# ESP32_DevKitC_v4.net
KiCad netlist of a schematic drawn in Altium Designer
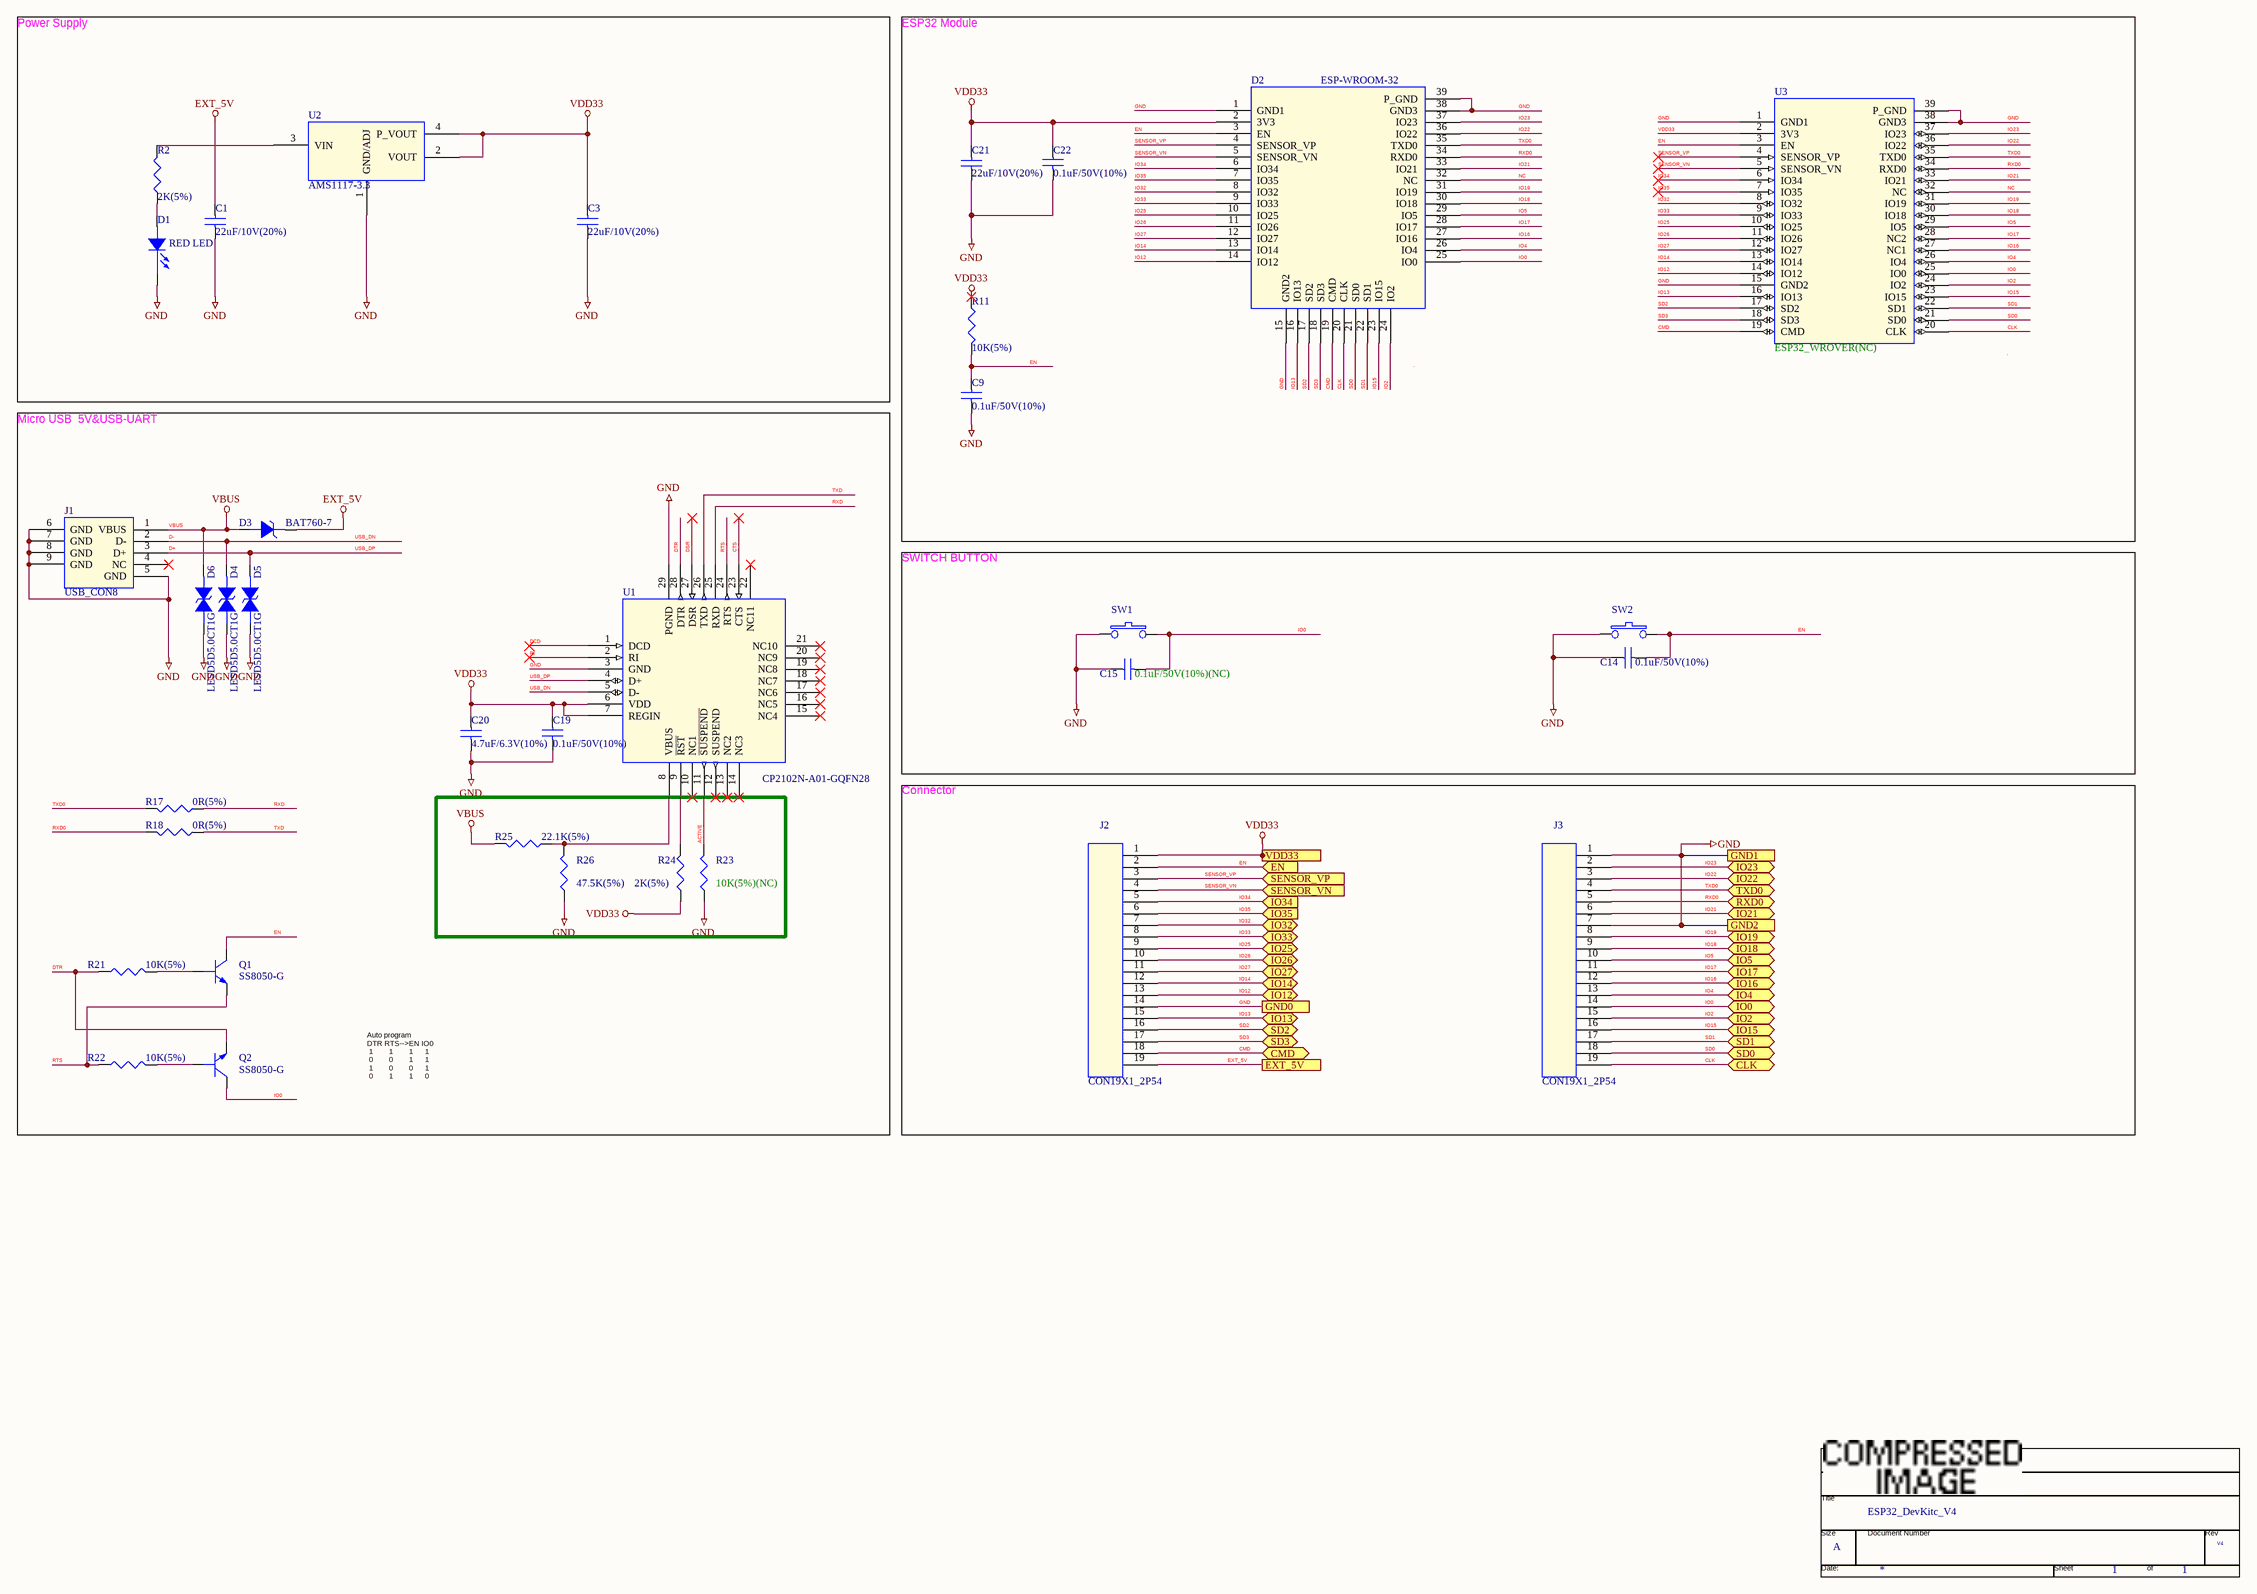
[diagram p0: ESP32_DevKitC_v4.SchDoc]

(export (version "E")
  (design (tool "Eeschema 10.0.6"))
  (components
    (comp (ref "*")
      (value "TitleBlock0")
      (fields
        (field (name "REVCODE") "V4")
        (field (name "TITLE") "ESP32_DevKitc_V4")
        (field (name "PAGE SIZE") "A")
        (field (name "PAGE NUMBER") "1")
        (field (name "PAGE COUNT") "1")
      )
      (libsource (lib "*") (part "TitleBlock0"))
    )
    (comp (ref "C1") (value "22uF/10V(20%)") (footprint "C0603") (libsource (lib "*") (part "CAP NP")))
    (comp (ref "C3") (value "22uF/10V(20%)") (footprint "C0603") (libsource (lib "*") (part "CAP NP")))
    (comp (ref "C9") (value "0.1uF/50V(10%)") (footprint "C0402") (libsource (lib "*") (part "CAP NP")))
    (comp (ref "C14") (value "0.1uF/50V(10%)") (footprint "C0402") (libsource (lib "*") (part "CAP NP")))
    (comp (ref "C15") (value "0.1uF/50V(10%)(NC)") (footprint "C0402") (libsource (lib "*") (part "CAP NP")))
    (comp (ref "C19") (value "0.1uF/50V(10%)") (footprint "C0402") (libsource (lib "*") (part "CAP NP")))
    (comp (ref "C20") (value "4.7uF/6.3V(10%)") (footprint "C0402") (libsource (lib "*") (part "CAP NP")))
    (comp (ref "C21") (value "22uF/10V(20%)") (footprint "C0603") (libsource (lib "*") (part "CAP NP")))
    (comp (ref "C22") (value "0.1uF/50V(10%)") (footprint "C0402") (libsource (lib "*") (part "CAP NP")))
    (comp (ref "D1") (value "RED LED") (footprint "0603D/A") (libsource (lib "*") (part "LED_1")))
    (comp (ref "D2")
      (value "ESP-WROOM-32")
      (footprint "ESP32_MODULE")
      (libsource (lib "*") (part "ESP32_MODULE_2"))
    )
    (comp (ref "D3") (value "BAT760-7") (footprint "SOD323") (libsource (lib "*") (part "DIODE_POWER_0")))
    (comp (ref "D4")
      (value "LESD5D5.0CT1G")
      (footprint "ESD0402")
      (libsource (lib "*") (part "DIODE BI-DIR TRIG"))
    )
    (comp (ref "D5")
      (value "LESD5D5.0CT1G")
      (footprint "ESD0402")
      (libsource (lib "*") (part "DIODE BI-DIR TRIG"))
    )
    (comp (ref "D6")
      (value "LESD5D5.0CT1G")
      (footprint "ESD0402")
      (libsource (lib "*") (part "DIODE BI-DIR TRIG"))
    )
    (comp (ref "J1") (value "USB_CON8") (footprint "USB_5P") (libsource (lib "*") (part "CON4_2")))
    (comp (ref "J2") (value "CON19X1_2P54") (footprint "CON19_2P54") (libsource (lib "*") (part "CON19_0")))
    (comp (ref "J3") (value "CON19X1_2P54") (footprint "CON19_2P54") (libsource (lib "*") (part "CON19_0")))
    (comp (ref "Q1") (value "SS8050-G") (footprint "SOT-23-3") (libsource (lib "*") (part "NPN BCE_0")))
    (comp (ref "Q2") (value "SS8050-G") (footprint "SOT-23-3") (libsource (lib "*") (part "NPN BCE_0")))
    (comp (ref "R2") (value "2K(5%)") (footprint "R0402") (libsource (lib "*") (part "RESISTOR_0")))
    (comp (ref "R11") (value "10K(5%)") (footprint "R0402") (libsource (lib "*") (part "RESISTOR_0")))
    (comp (ref "R17") (value "0R(5%)") (footprint "R0402") (libsource (lib "*") (part "RESISTOR_0")))
    (comp (ref "R18") (value "0R(5%)") (footprint "R0402") (libsource (lib "*") (part "RESISTOR_0")))
    (comp (ref "R21") (value "10K(5%)") (footprint "R0402") (libsource (lib "*") (part "RESISTOR_0")))
    (comp (ref "R22") (value "10K(5%)") (footprint "R0402") (libsource (lib "*") (part "RESISTOR_0")))
    (comp (ref "R23") (value "10K(5%)(NC)") (footprint "R0402") (libsource (lib "*") (part "RESISTOR_0")))
    (comp (ref "R24") (value "2K(5%)") (footprint "R0402") (libsource (lib "*") (part "RESISTOR_0")))
    (comp (ref "R25") (value "22.1K(5%)") (footprint "R0402") (libsource (lib "*") (part "RESISTOR_0")))
    (comp (ref "R26") (value "47.5K(5%)") (footprint "R0402") (libsource (lib "*") (part "RESISTOR_0")))
    (comp (ref "SW1")
      (value "SW PUSHBUTTON")
      (footprint "SW_3X4X2MM")
      (libsource (lib "*") (part "SW PUSHBUTTON"))
    )
    (comp (ref "SW2")
      (value "SW PUSHBUTTON")
      (footprint "SW_3X4X2MM")
      (libsource (lib "*") (part "SW PUSHBUTTON"))
    )
    (comp (ref "U1")
      (value "CP2102N-A01-GQFN28")
      (footprint "CP2102_QFN_28P")
      (libsource (lib "*") (part "CP2102_QFN_28"))
    )
    (comp (ref "U2") (value "AMS1117-3.3") (footprint "SOT-223") (libsource (lib "*") (part "NCP1117_0")))
    (comp (ref "U3")
      (value "ESP32_WROVER(NC)")
      (footprint "ESP32_MODULE_2COL")
      (libsource (lib "*") (part "ESP32_MODULE_3"))
    )
  )
  (nets
    (net (code "1") (name "/ACTIVE") (class "Default")
      (node (ref "R23") (pin "2") (pinfunction "2_2") (pintype "passive"))
      (node (ref "U1") (pin "11") (pinfunction "~{SUSPEND}_11") (pintype "output"))
    )
    (net (code "2") (name "/CLK") (class "Default")
      (node (ref "D2") (pin "20") (pinfunction "CLK_20") (pintype "passive"))
      (node (ref "J3") (pin "19") (pinfunction "19_19") (pintype "passive"))
      (node (ref "U3") (pin "20") (pinfunction "CLK_20") (pintype "bidirectional"))
    )
    (net (code "3") (name "/CMD") (class "Default")
      (node (ref "D2") (pin "19") (pinfunction "CMD_19") (pintype "passive"))
      (node (ref "J2") (pin "18") (pinfunction "18_18") (pintype "passive"))
      (node (ref "U3") (pin "19") (pinfunction "CMD_19") (pintype "bidirectional"))
    )
    (net (code "4") (name "/CTS") (class "Default")
      (node (ref "U1") (pin "23") (pinfunction "CTS_23") (pintype "input+no_connect"))
    )
    (net (code "5") (name "/D+") (class "Default")
      (node (ref "D5") (pin "1") (pinfunction "1_1") (pintype "passive"))
      (node (ref "J1") (pin "3") (pinfunction "D+_3") (pintype "passive"))
      (node (ref "U1") (pin "4") (pinfunction "D+_4") (pintype "bidirectional"))
    )
    (net (code "6") (name "/D-") (class "Default")
      (node (ref "D4") (pin "1") (pinfunction "1_1") (pintype "passive"))
      (node (ref "J1") (pin "2") (pinfunction "D-_2") (pintype "passive"))
      (node (ref "U1") (pin "5") (pinfunction "D-_5") (pintype "bidirectional"))
    )
    (net (code "7") (name "/DCD") (class "Default")
      (node (ref "U1") (pin "1") (pinfunction "DCD_1") (pintype "input+no_connect"))
    )
    (net (code "8") (name "/DSR") (class "Default")
      (node (ref "U1") (pin "27") (pinfunction "DSR_27") (pintype "input+no_connect"))
    )
    (net (code "9") (name "/DTR") (class "Default")
      (node (ref "Q2") (pin "2") (pinfunction "E_2") (pintype "passive"))
      (node (ref "R21") (pin "1") (pinfunction "1_1") (pintype "passive"))
      (node (ref "U1") (pin "28") (pinfunction "DTR_28") (pintype "output"))
    )
    (net (code "10") (name "/EN") (class "Default")
      (node (ref "C14") (pin "2") (pinfunction "2_2") (pintype "passive"))
      (node (ref "C9") (pin "1") (pinfunction "1_1") (pintype "passive"))
      (node (ref "D2") (pin "3") (pinfunction "EN_3") (pintype "passive"))
      (node (ref "J2") (pin "2") (pinfunction "2_2") (pintype "passive"))
      (node (ref "Q1") (pin "3") (pinfunction "C_3") (pintype "passive"))
      (node (ref "R11") (pin "2") (pinfunction "2_2") (pintype "passive"))
      (node (ref "SW2") (pin "2") (pinfunction "2_2") (pintype "passive"))
      (node (ref "U3") (pin "3") (pinfunction "EN_3") (pintype "passive"))
    )
    (net (code "11") (name "/IO0") (class "Default")
      (node (ref "C15") (pin "2") (pinfunction "2_2") (pintype "passive"))
      (node (ref "D2") (pin "25") (pinfunction "IO0_25") (pintype "passive"))
      (node (ref "J3") (pin "14") (pinfunction "14_14") (pintype "passive"))
      (node (ref "Q2") (pin "3") (pinfunction "C_3") (pintype "passive"))
      (node (ref "SW1") (pin "2") (pinfunction "2_2") (pintype "passive"))
      (node (ref "U3") (pin "25") (pinfunction "IO0_25") (pintype "bidirectional"))
    )
    (net (code "12") (name "/IO2") (class "Default")
      (node (ref "D2") (pin "24") (pinfunction "IO2_24") (pintype "passive"))
      (node (ref "J3") (pin "15") (pinfunction "15_15") (pintype "passive"))
      (node (ref "U3") (pin "24") (pinfunction "IO2_24") (pintype "bidirectional"))
    )
    (net (code "13") (name "/IO4") (class "Default")
      (node (ref "D2") (pin "26") (pinfunction "IO4_26") (pintype "passive"))
      (node (ref "J3") (pin "13") (pinfunction "13_13") (pintype "passive"))
      (node (ref "U3") (pin "26") (pinfunction "IO4_26") (pintype "bidirectional"))
    )
    (net (code "14") (name "/IO5") (class "Default")
      (node (ref "D2") (pin "29") (pinfunction "IO5_29") (pintype "passive"))
      (node (ref "J3") (pin "10") (pinfunction "10_10") (pintype "passive"))
      (node (ref "U3") (pin "29") (pinfunction "IO5_29") (pintype "bidirectional"))
    )
    (net (code "15") (name "/IO12") (class "Default")
      (node (ref "D2") (pin "14") (pinfunction "IO12_14") (pintype "passive"))
      (node (ref "J2") (pin "13") (pinfunction "13_13") (pintype "passive"))
      (node (ref "U3") (pin "14") (pinfunction "IO12_14") (pintype "bidirectional"))
    )
    (net (code "16") (name "/IO13") (class "Default")
      (node (ref "D2") (pin "16") (pinfunction "IO13_16") (pintype "passive"))
      (node (ref "J2") (pin "15") (pinfunction "15_15") (pintype "passive"))
      (node (ref "U3") (pin "16") (pinfunction "IO13_16") (pintype "bidirectional"))
    )
    (net (code "17") (name "/IO14") (class "Default")
      (node (ref "D2") (pin "13") (pinfunction "IO14_13") (pintype "passive"))
      (node (ref "J2") (pin "12") (pinfunction "12_12") (pintype "passive"))
      (node (ref "U3") (pin "13") (pinfunction "IO14_13") (pintype "bidirectional"))
    )
    (net (code "18") (name "/IO15") (class "Default")
      (node (ref "D2") (pin "23") (pinfunction "IO15_23") (pintype "passive"))
      (node (ref "J3") (pin "16") (pinfunction "16_16") (pintype "passive"))
      (node (ref "U3") (pin "23") (pinfunction "IO15_23") (pintype "bidirectional"))
    )
    (net (code "19") (name "/IO16") (class "Default")
      (node (ref "D2") (pin "27") (pinfunction "IO16_27") (pintype "passive"))
      (node (ref "J3") (pin "12") (pinfunction "12_12") (pintype "passive"))
      (node (ref "U3") (pin "27") (pinfunction "NC1_27") (pintype "bidirectional"))
    )
    (net (code "20") (name "/IO17") (class "Default")
      (node (ref "D2") (pin "28") (pinfunction "IO17_28") (pintype "passive"))
      (node (ref "J3") (pin "11") (pinfunction "11_11") (pintype "passive"))
      (node (ref "U3") (pin "28") (pinfunction "NC2_28") (pintype "bidirectional"))
    )
    (net (code "21") (name "/IO18") (class "Default")
      (node (ref "D2") (pin "30") (pinfunction "IO18_30") (pintype "passive"))
      (node (ref "J3") (pin "9") (pinfunction "9_9") (pintype "passive"))
      (node (ref "U3") (pin "30") (pinfunction "IO18_30") (pintype "bidirectional"))
    )
    (net (code "22") (name "/IO19") (class "Default")
      (node (ref "D2") (pin "31") (pinfunction "IO19_31") (pintype "passive"))
      (node (ref "J3") (pin "8") (pinfunction "8_8") (pintype "passive"))
      (node (ref "U3") (pin "31") (pinfunction "IO19_31") (pintype "bidirectional"))
    )
    (net (code "23") (name "/IO21") (class "Default")
      (node (ref "D2") (pin "33") (pinfunction "IO21_33") (pintype "passive"))
      (node (ref "J3") (pin "6") (pinfunction "6_6") (pintype "passive"))
      (node (ref "U3") (pin "33") (pinfunction "IO21_33") (pintype "bidirectional"))
    )
    (net (code "24") (name "/IO22") (class "Default")
      (node (ref "D2") (pin "36") (pinfunction "IO22_36") (pintype "passive"))
      (node (ref "J3") (pin "3") (pinfunction "3_3") (pintype "passive"))
      (node (ref "U3") (pin "36") (pinfunction "IO22_36") (pintype "bidirectional"))
    )
    (net (code "25") (name "/IO23") (class "Default")
      (node (ref "D2") (pin "37") (pinfunction "IO23_37") (pintype "passive"))
      (node (ref "J3") (pin "2") (pinfunction "2_2") (pintype "passive"))
      (node (ref "U3") (pin "37") (pinfunction "IO23_37") (pintype "bidirectional"))
    )
    (net (code "26") (name "/IO25") (class "Default")
      (node (ref "D2") (pin "10") (pinfunction "IO25_10") (pintype "passive"))
      (node (ref "J2") (pin "9") (pinfunction "9_9") (pintype "passive"))
      (node (ref "U3") (pin "10") (pinfunction "IO25_10") (pintype "bidirectional"))
    )
    (net (code "27") (name "/IO26") (class "Default")
      (node (ref "D2") (pin "11") (pinfunction "IO26_11") (pintype "passive"))
      (node (ref "J2") (pin "10") (pinfunction "10_10") (pintype "passive"))
      (node (ref "U3") (pin "11") (pinfunction "IO26_11") (pintype "bidirectional"))
    )
    (net (code "28") (name "/IO27") (class "Default")
      (node (ref "D2") (pin "12") (pinfunction "IO27_12") (pintype "passive"))
      (node (ref "J2") (pin "11") (pinfunction "11_11") (pintype "passive"))
      (node (ref "U3") (pin "12") (pinfunction "IO27_12") (pintype "bidirectional"))
    )
    (net (code "29") (name "/IO32") (class "Default")
      (node (ref "D2") (pin "8") (pinfunction "IO32_8") (pintype "passive"))
      (node (ref "J2") (pin "7") (pinfunction "7_7") (pintype "passive"))
      (node (ref "U3") (pin "8") (pinfunction "IO32_8") (pintype "bidirectional"))
    )
    (net (code "30") (name "/IO33") (class "Default")
      (node (ref "D2") (pin "9") (pinfunction "IO33_9") (pintype "passive"))
      (node (ref "J2") (pin "8") (pinfunction "8_8") (pintype "passive"))
      (node (ref "U3") (pin "9") (pinfunction "IO33_9") (pintype "bidirectional"))
    )
    (net (code "31") (name "/IO34") (class "Default")
      (node (ref "D2") (pin "6") (pinfunction "IO34_6") (pintype "passive"))
      (node (ref "J2") (pin "5") (pinfunction "5_5") (pintype "passive"))
      (node (ref "U3") (pin "6") (pinfunction "IO34_6") (pintype "input"))
    )
    (net (code "32") (name "/IO35") (class "Default")
      (node (ref "D2") (pin "7") (pinfunction "IO35_7") (pintype "passive"))
      (node (ref "J2") (pin "6") (pinfunction "6_6") (pintype "passive"))
      (node (ref "U3") (pin "7") (pinfunction "IO35_7") (pintype "input"))
    )
    (net (code "33") (name "/NC") (class "Default")
      (node (ref "D2") (pin "32") (pinfunction "NC_32") (pintype "passive"))
      (node (ref "U3") (pin "32") (pinfunction "NC_32") (pintype "bidirectional"))
    )
    (net (code "34") (name "/RI") (class "Default")
      (node (ref "U1") (pin "2") (pinfunction "RI_2") (pintype "input+no_connect"))
    )
    (net (code "35") (name "/RTS") (class "Default")
      (node (ref "Q1") (pin "2") (pinfunction "E_2") (pintype "passive"))
      (node (ref "R22") (pin "1") (pinfunction "1_1") (pintype "passive"))
      (node (ref "U1") (pin "24") (pinfunction "RTS_24") (pintype "output"))
    )
    (net (code "36") (name "/RXD") (class "Default")
      (node (ref "R17") (pin "1") (pinfunction "1_1") (pintype "passive"))
      (node (ref "U1") (pin "25") (pinfunction "RXD_25") (pintype "passive"))
    )
    (net (code "37") (name "/RXD0") (class "Default")
      (node (ref "D2") (pin "34") (pinfunction "RXD0_34") (pintype "passive"))
      (node (ref "J3") (pin "5") (pinfunction "5_5") (pintype "passive"))
      (node (ref "R18") (pin "2") (pinfunction "2_2") (pintype "passive"))
      (node (ref "U3") (pin "34") (pinfunction "RXD0_34") (pintype "bidirectional"))
    )
    (net (code "38") (name "/SD0") (class "Default")
      (node (ref "D2") (pin "21") (pinfunction "SD0_21") (pintype "passive"))
      (node (ref "J3") (pin "18") (pinfunction "18_18") (pintype "passive"))
      (node (ref "U3") (pin "21") (pinfunction "SD0_21") (pintype "bidirectional"))
    )
    (net (code "39") (name "/SD1") (class "Default")
      (node (ref "D2") (pin "22") (pinfunction "SD1_22") (pintype "passive"))
      (node (ref "J3") (pin "17") (pinfunction "17_17") (pintype "passive"))
      (node (ref "U3") (pin "22") (pinfunction "SD1_22") (pintype "bidirectional"))
    )
    (net (code "40") (name "/SD2") (class "Default")
      (node (ref "D2") (pin "17") (pinfunction "SD2_17") (pintype "passive"))
      (node (ref "J2") (pin "16") (pinfunction "16_16") (pintype "passive"))
      (node (ref "U3") (pin "17") (pinfunction "SD2_17") (pintype "bidirectional"))
    )
    (net (code "41") (name "/SD3") (class "Default")
      (node (ref "D2") (pin "18") (pinfunction "SD3_18") (pintype "passive"))
      (node (ref "J2") (pin "17") (pinfunction "17_17") (pintype "passive"))
      (node (ref "U3") (pin "18") (pinfunction "SD3_18") (pintype "bidirectional"))
    )
    (net (code "42") (name "/SENSOR_VN") (class "Default")
      (node (ref "D2") (pin "5") (pinfunction "SENSOR_VN_5") (pintype "passive"))
      (node (ref "J2") (pin "4") (pinfunction "4_4") (pintype "passive"))
      (node (ref "U3") (pin "5") (pinfunction "SENSOR_VN_5") (pintype "input"))
    )
    (net (code "43") (name "/SENSOR_VP") (class "Default")
      (node (ref "D2") (pin "4") (pinfunction "SENSOR_VP_4") (pintype "passive"))
      (node (ref "J2") (pin "3") (pinfunction "3_3") (pintype "passive"))
      (node (ref "U3") (pin "4") (pinfunction "SENSOR_VP_4") (pintype "input"))
    )
    (net (code "44") (name "/TXD") (class "Default")
      (node (ref "R18") (pin "1") (pinfunction "1_1") (pintype "passive"))
      (node (ref "U1") (pin "26") (pinfunction "TXD_26") (pintype "output"))
    )
    (net (code "45") (name "/TXD0") (class "Default")
      (node (ref "D2") (pin "35") (pinfunction "TXD0_35") (pintype "passive"))
      (node (ref "J3") (pin "4") (pinfunction "4_4") (pintype "passive"))
      (node (ref "R17") (pin "2") (pinfunction "2_2") (pintype "passive"))
      (node (ref "U3") (pin "35") (pinfunction "TXD0_35") (pintype "bidirectional"))
    )
    (net (code "46") (name "EXT_5V") (class "Default")
      (node (ref "C1") (pin "2") (pinfunction "2_2") (pintype "passive"))
      (node (ref "D3") (pin "1") (pinfunction "1_1") (pintype "passive"))
      (node (ref "J2") (pin "19") (pinfunction "19_19") (pintype "passive"))
    )
    (net (code "47") (name "GND") (class "Default")
      (node (ref "C1") (pin "1") (pinfunction "1_1") (pintype "passive"))
      (node (ref "C14") (pin "1") (pinfunction "1_1") (pintype "passive"))
      (node (ref "C15") (pin "1") (pinfunction "1_1") (pintype "passive"))
      (node (ref "C19") (pin "2") (pinfunction "2_2") (pintype "passive"))
      (node (ref "C20") (pin "1") (pinfunction "1_1") (pintype "passive"))
      (node (ref "C21") (pin "1") (pinfunction "1_1") (pintype "passive"))
      (node (ref "C22") (pin "2") (pinfunction "2_2") (pintype "passive"))
      (node (ref "C3") (pin "1") (pinfunction "1_1") (pintype "passive"))
      (node (ref "C9") (pin "2") (pinfunction "2_2") (pintype "passive"))
      (node (ref "D1") (pin "2") (pinfunction "CATHODE_2") (pintype "passive"))
      (node (ref "D2") (pin "1") (pinfunction "GND1_1") (pintype "power_in"))
      (node (ref "D2") (pin "15") (pinfunction "GND2_15") (pintype "power_in"))
      (node (ref "D2") (pin "38") (pinfunction "GND3_38") (pintype "passive"))
      (node (ref "D2") (pin "39") (pinfunction "P_GND_39") (pintype "power_in"))
      (node (ref "D4") (pin "2") (pinfunction "2_2") (pintype "passive"))
      (node (ref "D5") (pin "2") (pinfunction "2_2") (pintype "passive"))
      (node (ref "D6") (pin "2") (pinfunction "2_2") (pintype "passive"))
      (node (ref "J1") (pin "5") (pinfunction "GND_5") (pintype "power_in"))
      (node (ref "J1") (pin "6") (pinfunction "GND_6") (pintype "power_in"))
      (node (ref "J1") (pin "7") (pinfunction "GND_7") (pintype "power_in"))
      (node (ref "J1") (pin "8") (pinfunction "GND_8") (pintype "power_in"))
      (node (ref "J1") (pin "9") (pinfunction "GND_9") (pintype "power_in"))
      (node (ref "J2") (pin "14") (pinfunction "14_14") (pintype "passive"))
      (node (ref "J3") (pin "1") (pinfunction "1_1") (pintype "passive"))
      (node (ref "J3") (pin "7") (pinfunction "7_7") (pintype "passive"))
      (node (ref "R23") (pin "1") (pinfunction "1_1") (pintype "passive"))
      (node (ref "R26") (pin "1") (pinfunction "1_1") (pintype "passive"))
      (node (ref "SW1") (pin "1") (pinfunction "1_1") (pintype "passive"))
      (node (ref "SW2") (pin "1") (pinfunction "1_1") (pintype "passive"))
      (node (ref "U1") (pin "29") (pinfunction "PGND_29") (pintype "power_in"))
      (node (ref "U1") (pin "3") (pinfunction "GND_3") (pintype "power_in"))
      (node (ref "U2") (pin "1") (pinfunction "GND/ADJ_1") (pintype "passive"))
      (node (ref "U3") (pin "1") (pinfunction "GND1_1") (pintype "power_in"))
      (node (ref "U3") (pin "15") (pinfunction "GND2_15") (pintype "power_in"))
      (node (ref "U3") (pin "38") (pinfunction "GND3_38") (pintype "power_in"))
      (node (ref "U3") (pin "39") (pinfunction "P_GND_39") (pintype "power_in"))
    )
    (net (code "48") (name "Net-(D1-ANODE)") (class "Default")
      (node (ref "D1") (pin "1") (pinfunction "ANODE_1") (pintype "passive"))
      (node (ref "R2") (pin "2") (pinfunction "2_2") (pintype "passive"))
    )
    (net (code "49") (name "Net-(Q1-B)") (class "Default")
      (node (ref "Q1") (pin "1") (pinfunction "B_1") (pintype "passive"))
      (node (ref "R21") (pin "2") (pinfunction "2_2") (pintype "passive"))
    )
    (net (code "50") (name "Net-(Q2-B)") (class "Default")
      (node (ref "Q2") (pin "1") (pinfunction "B_1") (pintype "passive"))
      (node (ref "R22") (pin "2") (pinfunction "2_2") (pintype "passive"))
    )
    (net (code "51") (name "Net-(U1-VBUS)") (class "Default")
      (node (ref "R25") (pin "1") (pinfunction "1_1") (pintype "passive"))
      (node (ref "R26") (pin "2") (pinfunction "2_2") (pintype "passive"))
      (node (ref "U1") (pin "8") (pinfunction "VBUS_8") (pintype "power_in"))
    )
    (net (code "52") (name "Net-(U1-~{RST})") (class "Default")
      (node (ref "R24") (pin "2") (pinfunction "2_2") (pintype "passive"))
      (node (ref "U1") (pin "9") (pinfunction "~{RST}_9") (pintype "passive"))
    )
    (net (code "53") (name "Net-(U2-VIN)") (class "Default")
      (node (ref "R2") (pin "1") (pinfunction "1_1") (pintype "passive"))
      (node (ref "U2") (pin "3") (pinfunction "VIN_3") (pintype "power_in"))
    )
    (net (code "54") (name "VBUS") (class "Default")
      (node (ref "D3") (pin "2") (pinfunction "2_2") (pintype "passive"))
      (node (ref "D6") (pin "1") (pinfunction "1_1") (pintype "passive"))
      (node (ref "J1") (pin "1") (pinfunction "VBUS_1") (pintype "power_in"))
      (node (ref "R25") (pin "2") (pinfunction "2_2") (pintype "passive"))
    )
    (net (code "55") (name "VDD33") (class "Default")
      (node (ref "C19") (pin "1") (pinfunction "1_1") (pintype "passive"))
      (node (ref "C20") (pin "2") (pinfunction "2_2") (pintype "passive"))
      (node (ref "C21") (pin "2") (pinfunction "2_2") (pintype "passive"))
      (node (ref "C22") (pin "1") (pinfunction "1_1") (pintype "passive"))
      (node (ref "C3") (pin "2") (pinfunction "2_2") (pintype "passive"))
      (node (ref "D2") (pin "2") (pinfunction "3V3_2") (pintype "power_in"))
      (node (ref "J2") (pin "1") (pinfunction "1_1") (pintype "passive"))
      (node (ref "R11") (pin "1") (pinfunction "1_1") (pintype "passive"))
      (node (ref "R24") (pin "1") (pinfunction "1_1") (pintype "passive"))
      (node (ref "U1") (pin "6") (pinfunction "VDD_6") (pintype "power_in"))
      (node (ref "U1") (pin "7") (pinfunction "REGIN_7") (pintype "power_in"))
      (node (ref "U2") (pin "2") (pinfunction "VOUT_2") (pintype "power_in"))
      (node (ref "U2") (pin "4") (pinfunction "P_VOUT_4") (pintype "power_in"))
      (node (ref "U3") (pin "2") (pinfunction "3V3_2") (pintype "power_in"))
    )
    (net (code "56") (name "unconnected-(J1-NC-Pad4)") (class "Default")
      (node (ref "J1") (pin "4") (pinfunction "NC_4") (pintype "passive+no_connect"))
    )
    (net (code "57") (name "unconnected-(U1-NC1-Pad10)") (class "Default")
      (node (ref "U1") (pin "10") (pinfunction "NC1_10") (pintype "passive+no_connect"))
    )
    (net (code "58") (name "unconnected-(U1-NC2-Pad13)") (class "Default")
      (node (ref "U1") (pin "13") (pinfunction "NC2_13") (pintype "passive+no_connect"))
    )
    (net (code "59") (name "unconnected-(U1-NC3-Pad14)") (class "Default")
      (node (ref "U1") (pin "14") (pinfunction "NC3_14") (pintype "passive+no_connect"))
    )
    (net (code "60") (name "unconnected-(U1-NC4-Pad15)") (class "Default")
      (node (ref "U1") (pin "15") (pinfunction "NC4_15") (pintype "passive+no_connect"))
    )
    (net (code "61") (name "unconnected-(U1-NC5-Pad16)") (class "Default")
      (node (ref "U1") (pin "16") (pinfunction "NC5_16") (pintype "passive+no_connect"))
    )
    (net (code "62") (name "unconnected-(U1-NC6-Pad17)") (class "Default")
      (node (ref "U1") (pin "17") (pinfunction "NC6_17") (pintype "passive+no_connect"))
    )
    (net (code "63") (name "unconnected-(U1-NC7-Pad18)") (class "Default")
      (node (ref "U1") (pin "18") (pinfunction "NC7_18") (pintype "passive+no_connect"))
    )
    (net (code "64") (name "unconnected-(U1-NC8-Pad19)") (class "Default")
      (node (ref "U1") (pin "19") (pinfunction "NC8_19") (pintype "passive+no_connect"))
    )
    (net (code "65") (name "unconnected-(U1-NC9-Pad20)") (class "Default")
      (node (ref "U1") (pin "20") (pinfunction "NC9_20") (pintype "passive+no_connect"))
    )
    (net (code "66") (name "unconnected-(U1-NC10-Pad21)") (class "Default")
      (node (ref "U1") (pin "21") (pinfunction "NC10_21") (pintype "passive+no_connect"))
    )
    (net (code "67") (name "unconnected-(U1-NC11-Pad22)") (class "Default")
      (node (ref "U1") (pin "22") (pinfunction "NC11_22") (pintype "passive+no_connect"))
    )
    (net (code "68") (name "unconnected-(U1-SUSPEND-Pad12)") (class "Default")
      (node (ref "U1") (pin "12") (pinfunction "SUSPEND_12") (pintype "output+no_connect"))
    )
  )
)
